# AOut_Isolator.net
KiCad netlist of a schematic drawn in Altium Designer
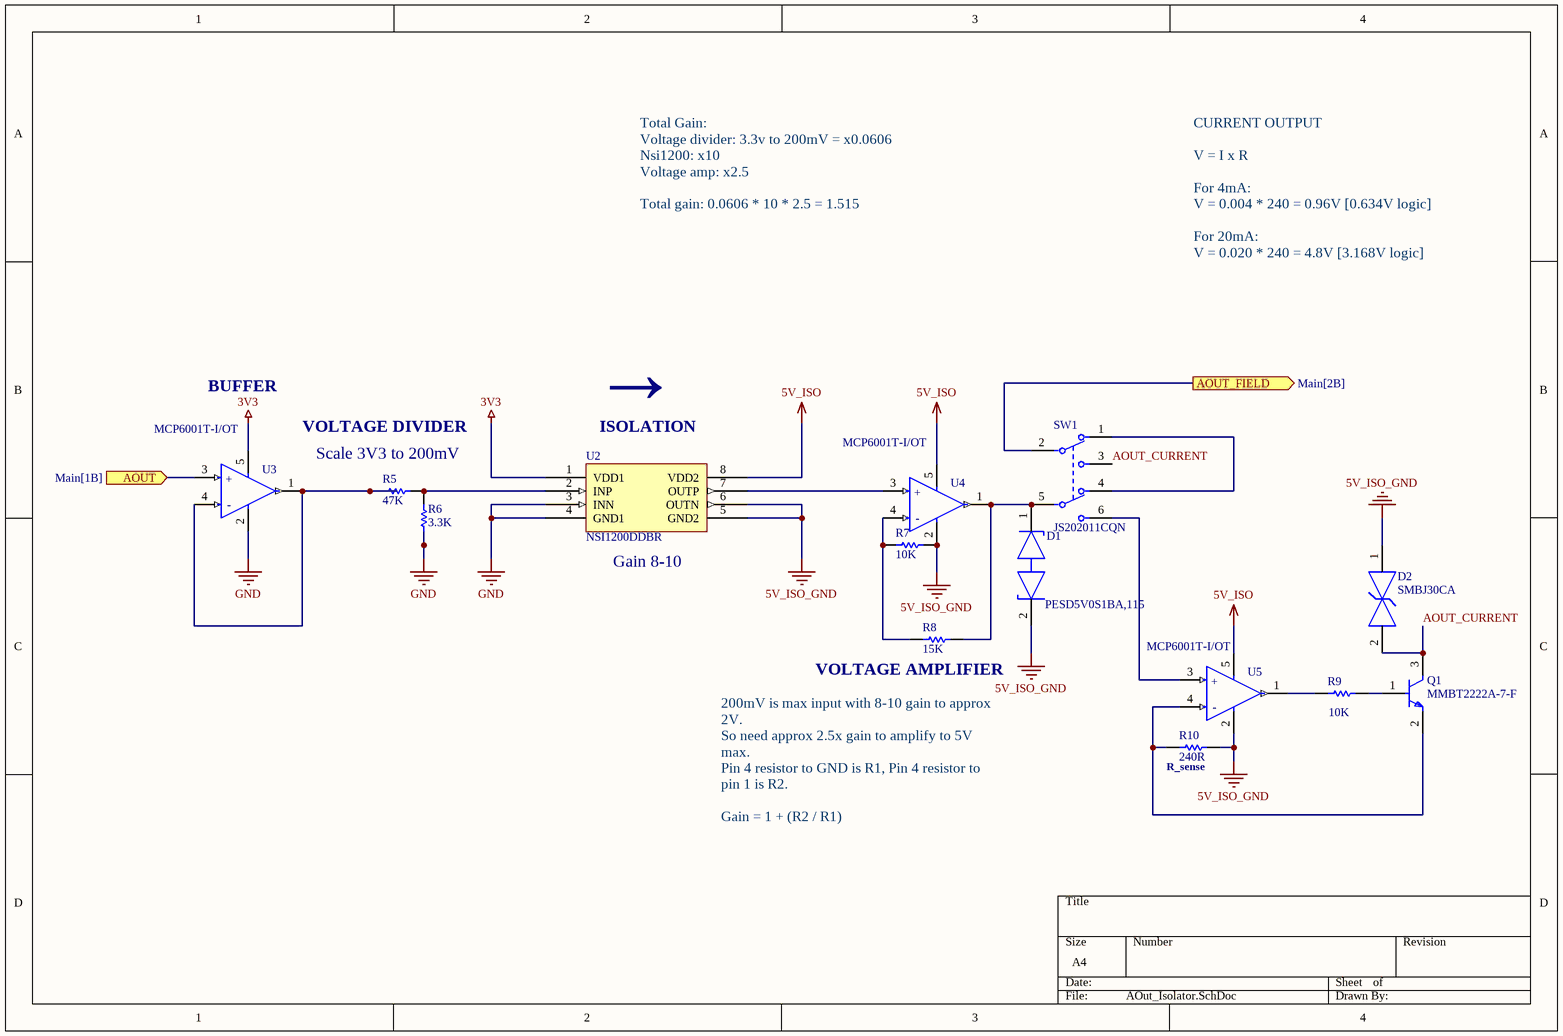
[diagram p0: AOut_Isolator.SchDoc]

(export (version "E")
  (design (tool "Eeschema 10.0.6"))
  (components
    (comp (ref "D1")
      (value "PESD5V0S1BA,115")
      (footprint "FP-SOD323-CA-MFG")
      (description "TVS DIODE 5V 14V SOD323")
      (libsource (lib "Altium Content Vault") (part "f6dbb2535d6b2d347ec798cb4d032a4"))
    )
    (comp (ref "D2")
      (value "SMBJ30CA")
      (footprint "FP-SMBJ30CAHE3-52-MFG")
      (description "TVS DIODE 30V 48.4V DO214AA")
      (fields
        (field (name "OCTOPART") "https://octopart.com/smbj30cahe3%2F52-vishay-43725255")
        (field (name "MANUFACTURER") "Vishay Semiconductor Diodes Division")
      )
      (libsource (lib "Altium Content Vault") (part "876f4347bf90aa6f500f43e3cd03972"))
    )
    (comp (ref "Q1")
      (value "MMBT2222A-7-F")
      (footprint "FP-SOT23-IPC_A")
      (description "TRANS NPN 40V 0.6A SMD SOT23-3")
      (fields (field (name "VOLTAGE") "40V"))
      (libsource (lib "Altium Content Vault") (part "b44e953556f554d0102664c7d152cb4"))
    )
    (comp (ref "R5")
      (value "47K")
      (footprint "RESC1608X55X30NL15T15")
      (description "Chip Resistor, 47 KOhm, +/- 1%, 0.1 W, -55 to 155 degC, 0603 (1608 Metric), RoHS, Tape and Reel")
      (libsource (lib "Altium Content Vault") (part "RES-2"))
    )
    (comp (ref "R6")
      (value "3.3K")
      (footprint "RESC1609X55X30ML15T15")
      (description "Chip Resistors, 3.3 KOhm, +/- 1%, 0.1 W, 0603 (1608 Metric), -55 to 155 degC, RoHS, Tape and Reel")
      (fields (field (name "MANUFACTURER") "Panasonic") (field (name "TOLERANCE") "1%"))
      (libsource (lib "Altium Content Vault") (part "RES-2"))
    )
    (comp (ref "R7")
      (value "10K")
      (footprint "RESC1609X55X30LL15T15")
      (description "Chip Resistor, 10 KOhm, +/- 1%, 0.1 W, -55 to 155 degC, 0603 (1608 Metric), RoHS, Tape and Reel")
      (fields (field (name "TOLERANCE") "1%") (field (name "MANUFACTURER") "Panasonic"))
      (libsource (lib "Altium Content Vault") (part "RES-2"))
    )
    (comp (ref "R8")
      (value "15K")
      (footprint "RESC1608X55X30NL15T15")
      (fields (field (name "PART NUMBER") "ERJ-3EKF1502V") (field (name "MANUFACTURER") "Panasonic"))
      (libsource (lib "Altium Content Vault") (part "RES"))
    )
    (comp (ref "R9")
      (value "10K")
      (footprint "RESC1609X55X30LL15T15")
      (description "Chip Resistor, 10 KOhm, +/- 1%, 0.1 W, -55 to 155 degC, 0603 (1608 Metric), RoHS, Tape and Reel")
      (fields (field (name "TOLERANCE") "1%") (field (name "MANUFACTURER") "Panasonic"))
      (libsource (lib "Altium Content Vault") (part "RES-2"))
    )
    (comp (ref "R10")
      (value "240R")
      (footprint "RESC3216X70X50NL05T20")
      (fields (field (name "PART NUMBER") "ERJ-8GEYJ241V") (field (name "MANUFACTURER") "Panasonic"))
      (libsource (lib "Altium Content Vault") (part "RES"))
    )
    (comp (ref "SW1")
      (value "JS202011CQN")
      (footprint "FP-JS202011CQN-MFG")
      (description "SWITCH SLIDE DPDT 300MA 6V")
      (libsource (lib "Altium Content Vault") (part "a9e2ad50e97b660f430b512a9354c8c"))
    )
    (comp (ref "U2")
      (value "NSI1200DDBR")
      (footprint "NSI1200DDBR")
      (description "High Reliability Reinforced Isolated Amplifier")
      (fields (field (name "MANUFACTURER") "Novosense"))
      (libsource (lib "nsi1200") (part "NSI1200DDBR"))
    )
    (comp (ref "U3")
      (value "MCP6001T-I/OT")
      (footprint "FP-C04-091-OT-IPC_A")
      (description "IC OPAMP GP 1 CIRCUIT SOT23-5")
      (fields (field (name "VOLTAGE") "6V"))
      (libsource (lib "Altium Content Vault") (part "c8a8c153b9e84e05c1733c8ea85bdd9"))
    )
    (comp (ref "U4")
      (value "MCP6001T-I/OT")
      (footprint "FP-C04-091-OT-IPC_A")
      (description "IC OPAMP GP 1 CIRCUIT SOT23-5")
      (fields (field (name "VOLTAGE") "6V"))
      (libsource (lib "Altium Content Vault") (part "c8a8c153b9e84e05c1733c8ea85bdd9"))
    )
    (comp (ref "U5")
      (value "MCP6001T-I/OT")
      (footprint "FP-C04-091-OT-IPC_A")
      (description "IC OPAMP GP 1 CIRCUIT SOT23-5")
      (fields (field (name "VOLTAGE") "6V"))
      (libsource (lib "Altium Content Vault") (part "c8a8c153b9e84e05c1733c8ea85bdd9"))
    )
  )
  (nets
    (net (code "1") (name "/AOUT") (class "Default")
      (node (ref "U3") (pin "3") (pinfunction "VIN+_3") (pintype "input"))
    )
    (net (code "2") (name "/AOUT_CURRENT") (class "Default")
      (node (ref "D2") (pin "2") (pinfunction "2_2") (pintype "passive"))
      (node (ref "Q1") (pin "3") (pinfunction "C_3") (pintype "passive"))
      (node (ref "SW1") (pin "3") (pinfunction "3_3") (pintype "passive"))
    )
    (net (code "3") (name "/AOUT_FIELD") (class "Default")
      (node (ref "SW1") (pin "2") (pinfunction "2_2") (pintype "passive"))
    )
    (net (code "4") (name "3V3") (class "Default")
      (node (ref "U2") (pin "1") (pinfunction "VDD1_1") (pintype "power_in"))
      (node (ref "U3") (pin "5") (pinfunction "VDD_5") (pintype "power_in"))
    )
    (net (code "5") (name "5V_ISO") (class "Default")
      (node (ref "U2") (pin "8") (pinfunction "VDD2_8") (pintype "power_in"))
      (node (ref "U4") (pin "5") (pinfunction "VDD_5") (pintype "power_in"))
      (node (ref "U5") (pin "5") (pinfunction "VDD_5") (pintype "power_in"))
    )
    (net (code "6") (name "5V_ISO_GND") (class "Default")
      (node (ref "D1") (pin "2") (pinfunction "K2_2") (pintype "passive"))
      (node (ref "D2") (pin "1") (pinfunction "1_1") (pintype "passive"))
      (node (ref "R10") (pin "1") (pinfunction "1_1") (pintype "passive"))
      (node (ref "R7") (pin "2") (pinfunction "2_2") (pintype "passive"))
      (node (ref "U2") (pin "5") (pinfunction "GND2_5") (pintype "power_in"))
      (node (ref "U2") (pin "6") (pinfunction "OUTN_6") (pintype "output"))
      (node (ref "U4") (pin "2") (pinfunction "VSS_2") (pintype "power_in"))
      (node (ref "U5") (pin "2") (pinfunction "VSS_2") (pintype "power_in"))
    )
    (net (code "7") (name "GND") (class "Default")
      (node (ref "R6") (pin "2") (pinfunction "2_2") (pintype "passive"))
      (node (ref "U2") (pin "3") (pinfunction "INN_3") (pintype "input"))
      (node (ref "U2") (pin "4") (pinfunction "GND1_4") (pintype "power_in"))
      (node (ref "U3") (pin "2") (pinfunction "VSS_2") (pintype "power_in"))
    )
    (net (code "8") (name "Net-(D1-K1)") (class "Default")
      (node (ref "D1") (pin "1") (pinfunction "K1_1") (pintype "passive"))
      (node (ref "R8") (pin "2") (pinfunction "2_2") (pintype "passive"))
      (node (ref "SW1") (pin "5") (pinfunction "5_5") (pintype "passive"))
      (node (ref "U4") (pin "1") (pinfunction "VOUT_1") (pintype "output"))
    )
    (net (code "9") (name "Net-(Q1-B)") (class "Default")
      (node (ref "Q1") (pin "1") (pinfunction "B_1") (pintype "passive"))
      (node (ref "R9") (pin "2") (pinfunction "2_2") (pintype "passive"))
    )
    (net (code "10") (name "Net-(Q1-E)") (class "Default")
      (node (ref "Q1") (pin "2") (pinfunction "E_2") (pintype "passive"))
      (node (ref "R10") (pin "2") (pinfunction "2_2") (pintype "passive"))
      (node (ref "U5") (pin "4") (pinfunction "VIN-_4") (pintype "input"))
    )
    (net (code "11") (name "Net-(SW1-Pad1)") (class "Default")
      (node (ref "SW1") (pin "1") (pinfunction "1_1") (pintype "passive"))
      (node (ref "SW1") (pin "4") (pinfunction "4_4") (pintype "passive"))
    )
    (net (code "12") (name "Net-(U2-INP)") (class "Default")
      (node (ref "R5") (pin "2") (pinfunction "2_2") (pintype "passive"))
      (node (ref "R6") (pin "1") (pinfunction "1_1") (pintype "passive"))
      (node (ref "U2") (pin "2") (pinfunction "INP_2") (pintype "input"))
    )
    (net (code "13") (name "Net-(U2-OUTP)") (class "Default")
      (node (ref "U2") (pin "7") (pinfunction "OUTP_7") (pintype "output"))
      (node (ref "U4") (pin "3") (pinfunction "VIN+_3") (pintype "input"))
    )
    (net (code "14") (name "Net-(U3-VIN-)") (class "Default")
      (node (ref "R5") (pin "1") (pinfunction "1_1") (pintype "passive"))
      (node (ref "U3") (pin "1") (pinfunction "VOUT_1") (pintype "output"))
      (node (ref "U3") (pin "4") (pinfunction "VIN-_4") (pintype "input"))
    )
    (net (code "15") (name "Net-(U4-VIN-)") (class "Default")
      (node (ref "R7") (pin "1") (pinfunction "1_1") (pintype "passive"))
      (node (ref "R8") (pin "1") (pinfunction "1_1") (pintype "passive"))
      (node (ref "U4") (pin "4") (pinfunction "VIN-_4") (pintype "input"))
    )
    (net (code "16") (name "Net-(U5-VIN+)") (class "Default")
      (node (ref "SW1") (pin "6") (pinfunction "6_6") (pintype "passive"))
      (node (ref "U5") (pin "3") (pinfunction "VIN+_3") (pintype "input"))
    )
    (net (code "17") (name "Net-(U5-VOUT)") (class "Default")
      (node (ref "R9") (pin "1") (pinfunction "1_1") (pintype "passive"))
      (node (ref "U5") (pin "1") (pinfunction "VOUT_1") (pintype "output"))
    )
  )
)
